# ISL6236A_DEMO.net
KiCad netlist of a schematic drawn in Altium Designer
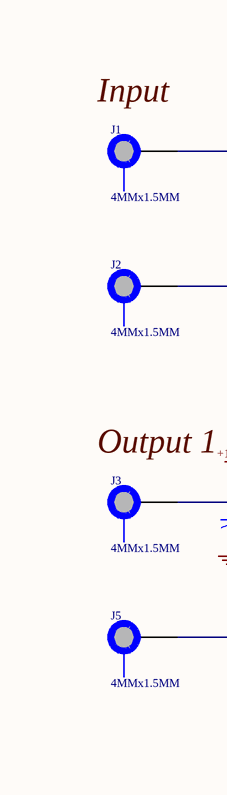
[diagram p0: ISL6236A_DEMO.SchDoc, left]
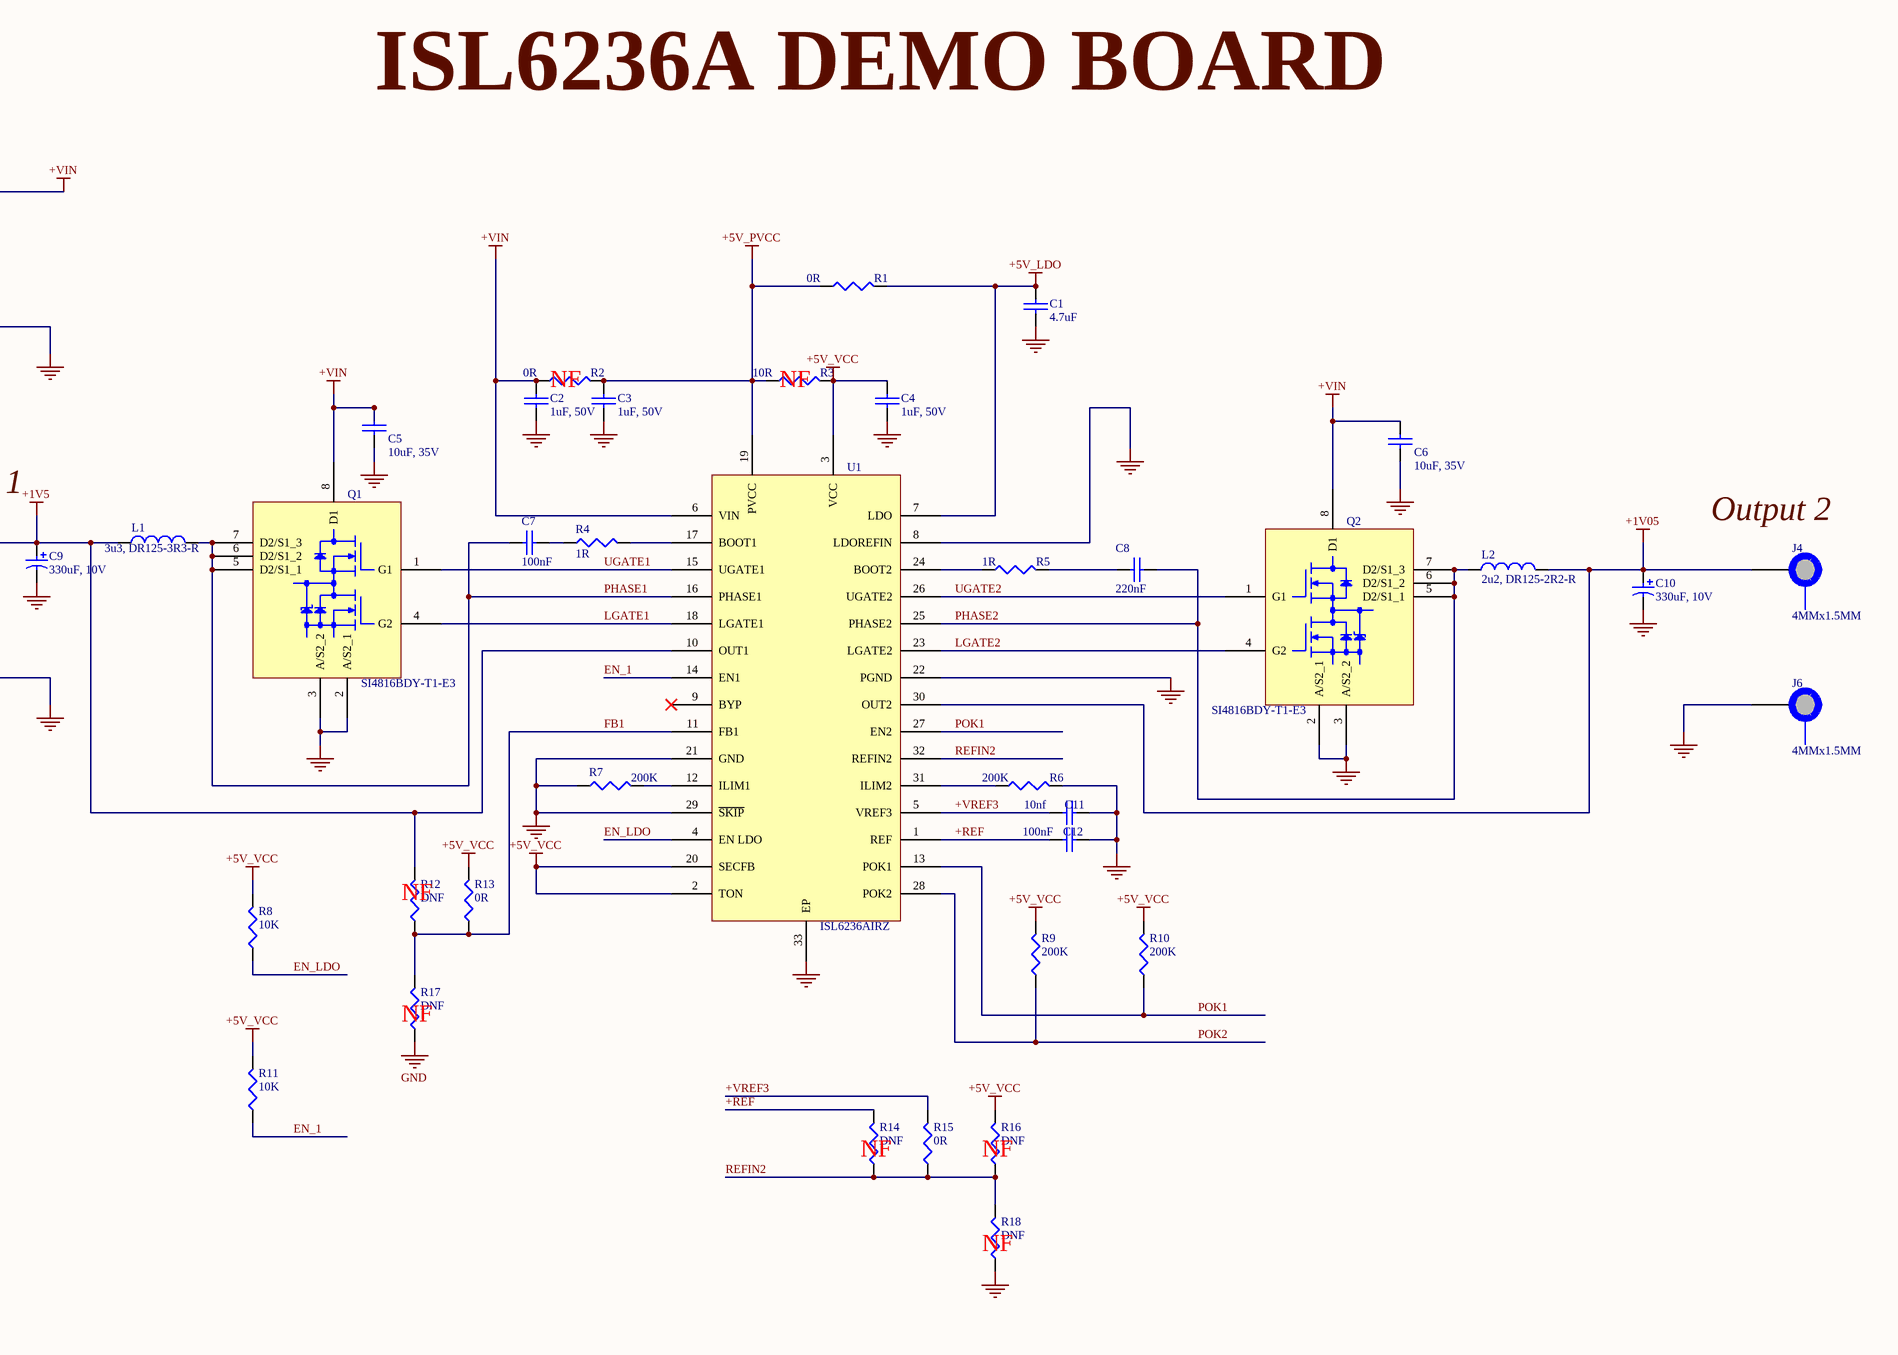
[diagram p1: ISL6236A_DEMO.SchDoc, right]

(export (version "E")
  (design (tool "Eeschema 10.0.6"))
  (components
    (comp (ref "C1")
      (value "4.7uF")
      (description "C Series 1206 4.7 uF 50 V ±10 % Tolerance X5R SMT Multilayer Ceramic Capacitor")
      (fields
        (field (name "MANUFACTURER") "TDK")
        (field (name "MANUFACTURER PART NUMBER") "C3216X5R1H475K160AB")
      )
      (libsource (lib "ISL6236A_DEMO") (part "C3216X5R1H475K160AB"))
    )
    (comp (ref "C2")
      (value "1uF, 50V")
      (description "C Series 0805 1 uF 50 V ±10% Tolerance X7R SMT Multilayer Ceramic Capacitor")
      (fields
        (field (name "MANUFACTURER") "TDK")
        (field (name "MANUFACTURER PART NUMBER") "C2012X7R1H105K125AB")
      )
      (libsource (lib "ISL6236A_DEMO") (part "C2012X7R1H105K125AB"))
    )
    (comp (ref "C3")
      (value "1uF, 50V")
      (description "C Series 0805 1 uF 50 V ±10% Tolerance X7R SMT Multilayer Ceramic Capacitor")
      (fields
        (field (name "MANUFACTURER") "TDK")
        (field (name "MANUFACTURER PART NUMBER") "C2012X7R1H105K125AB")
      )
      (libsource (lib "ISL6236A_DEMO") (part "C2012X7R1H105K125AB"))
    )
    (comp (ref "C4")
      (value "1uF, 50V")
      (description "C Series 0805 1 uF 50 V ±10% Tolerance X7R SMT Multilayer Ceramic Capacitor")
      (fields
        (field (name "MANUFACTURER") "TDK")
        (field (name "MANUFACTURER PART NUMBER") "C2012X7R1H105K125AB")
      )
      (libsource (lib "ISL6236A_DEMO") (part "C2012X7R1H105K125AB"))
    )
    (comp (ref "C5")
      (value "10uF, 35V")
      (fields
        (field (name "MANUFACTURER") "Yageo Group")
        (field (name "MANUFACTURER PART NUMBER") "C1210C106K6PAC7210")
        (field (name "TOLERANCE") "10%")
      )
      (libsource (lib "ISL6236A_DEMO") (part "C1210C106K6PAC7210"))
    )
    (comp (ref "C6")
      (value "10uF, 35V")
      (fields
        (field (name "MANUFACTURER") "Yageo Group")
        (field (name "MANUFACTURER PART NUMBER") "C1210C106K6PAC7210")
        (field (name "TOLERANCE") "10%")
      )
      (libsource (lib "ISL6236A_DEMO") (part "C1210C106K6PAC7210"))
    )
    (comp (ref "C7")
      (value "100nF")
      (description "Cap Ceramic 0.1uF 50V X7R 10% Pad SMD 0805 Flexible Termination 125C Automotive Medical T/R")
      (fields
        (field (name "MANUFACTURER") "Yageo Group")
        (field (name "MANUFACTURER PART NUMBER") "C0805X104K5RACTU")
      )
      (libsource (lib "ISL6236A_DEMO") (part "C0805X104K5RACTU"))
    )
    (comp (ref "C8")
      (value "220nF")
      (description "50V 220nF X7R ±10% 0805 Multilayer Ceramic Capacitors MLCC - SMD/SMT ROHS")
      (fields
        (field (name "MANUFACTURER") "Yageo Group")
        (field (name "MANUFACTURER PART NUMBER") "C0805C224K5RACTU")
      )
      (libsource (lib "ISL6236A_DEMO") (part "C0805C224K5RACTU"))
    )
    (comp (ref "C9")
      (value "330uF, 10V")
      (description "Cap Tant Solid 330uF 10V X CASE 20% (7.3 X 4.3 X 4mm) SMD 7343-43 T/R")
      (fields
        (field (name "MANUFACTURER") "Yageo Group")
        (field (name "MANUFACTURER PART NUMBER") "T530X337M010ATE004")
      )
      (libsource (lib "ISL6236A_DEMO") (part "T530X337M010ATE004"))
    )
    (comp (ref "C10")
      (value "330uF, 10V")
      (description "Cap Tant Solid 330uF 10V X CASE 20% (7.3 X 4.3 X 4mm) SMD 7343-43 T/R")
      (fields
        (field (name "MANUFACTURER") "Yageo Group")
        (field (name "MANUFACTURER PART NUMBER") "T530X337M010ATE004")
      )
      (libsource (lib "ISL6236A_DEMO") (part "T530X337M010ATE004"))
    )
    (comp (ref "C11")
      (value "10nf")
      (description "Multilayer Ceramic Capacitors Mlcc - Smd/Smt 50V 0.01Uf X7R 0805 10%")
      (fields
        (field (name "MANUFACTURER") "Yageo Group")
        (field (name "MANUFACTURER PART NUMBER") "C0805C103K5RACTU")
      )
      (libsource (lib "ISL6236A_DEMO") (part "C0805C103K5RACTU"))
    )
    (comp (ref "C12")
      (value "100nF")
      (description "Cap Ceramic 0.1uF 50V X7R 10% Pad SMD 0805 Flexible Termination 125C Automotive Medical T/R")
      (fields
        (field (name "MANUFACTURER") "Yageo Group")
        (field (name "MANUFACTURER PART NUMBER") "C0805X104K5RACTU")
      )
      (libsource (lib "ISL6236A_DEMO") (part "C0805X104K5RACTU"))
    )
    (comp (ref "J1")
      (value "4MMx1.5MM")
      (description "pad with a hole 4mm x 1.5mm")
      (libsource (lib "ISL6236A_DEMO") (part "PAD_WITH_HOLE_4MM_1MM5"))
    )
    (comp (ref "J2")
      (value "4MMx1.5MM")
      (description "pad with a hole 4mm x 1.5mm")
      (libsource (lib "ISL6236A_DEMO") (part "PAD_WITH_HOLE_4MM_1MM5"))
    )
    (comp (ref "J3")
      (value "4MMx1.5MM")
      (description "pad with a hole 4mm x 1.5mm")
      (libsource (lib "ISL6236A_DEMO") (part "PAD_WITH_HOLE_4MM_1MM5"))
    )
    (comp (ref "J4")
      (value "4MMx1.5MM")
      (description "pad with a hole 4mm x 1.5mm")
      (libsource (lib "ISL6236A_DEMO") (part "PAD_WITH_HOLE_4MM_1MM5"))
    )
    (comp (ref "J5")
      (value "4MMx1.5MM")
      (description "pad with a hole 4mm x 1.5mm")
      (libsource (lib "ISL6236A_DEMO") (part "PAD_WITH_HOLE_4MM_1MM5"))
    )
    (comp (ref "J6")
      (value "4MMx1.5MM")
      (description "pad with a hole 4mm x 1.5mm")
      (libsource (lib "ISL6236A_DEMO") (part "PAD_WITH_HOLE_4MM_1MM5"))
    )
    (comp (ref "L1")
      (value "3u3, DR125-3R3-R")
      (description "Inductor Power Shielded Drum Core 3.3uH 20% 100KHz Ferrite 9.26A 6.3mOhm DCR T/R")
      (fields (field (name "MANUFACTURER") "Eaton") (field (name "MANUFACTURER PART NUMBER") "DR125-3R3-R"))
      (libsource (lib "ISL6236A_DEMO") (part "DR125-3R3-R"))
    )
    (comp (ref "L2")
      (value "2u2, DR125-2R2-R")
      (description "Inductor Power Shielded Drum Core 2.2uH 20% 100KHz Ferrite 10.9A 4.5mOhm DCR T/R")
      (fields (field (name "MANUFACTURER") "Eaton") (field (name "MANUFACTURER PART NUMBER") "DR125-2R2-R"))
      (libsource (lib "ISL6236A_DEMO") (part "DR125-2R2-R"))
    )
    (comp (ref "Q1")
      (value "SI4816BDY-T1-E3")
      (description "Transistor MOSFET Array Dual N-CH 30V 5.8A/8.2A 8-Pin SOIC T/R")
      (fields (field (name "MANUFACTURER") "Vishay"))
      (libsource (lib "ISL6236A_DEMO") (part "SI4816BDY-T1-E3"))
    )
    (comp (ref "Q2")
      (value "SI4816BDY-T1-E3")
      (description "Transistor MOSFET Array Dual N-CH 30V 5.8A/8.2A 8-Pin SOIC T/R")
      (fields (field (name "MANUFACTURER") "Vishay"))
      (libsource (lib "") (part "SI4816BDY-T1-E3_1"))
    )
    (comp (ref "R1")
      (value "0R")
      (description "Zero Ohm Resistor, Jumper, 0805 [2012 Metric], Thick Film, 125 mW, 2 A, Surface Mount Device")
      (fields
        (field (name "MANUFACTURER") "Yageo Group")
        (field (name "MANUFACTURER PART NUMBER") "AC0805JR-070RL")
      )
      (libsource (lib "ISL6236A_DEMO") (part "AC0805JR-070RL"))
    )
    (comp (ref "R2")
      (value "0R")
      (description "Zero Ohm Resistor, Jumper, 0805 [2012 Metric], Thick Film, 125 mW, 2 A, Surface Mount Device")
      (fields
        (field (name "MANUFACTURER") "Yageo Group")
        (field (name "MANUFACTURER PART NUMBER") "AC0805JR-070RL")
      )
      (libsource (lib "ISL6236A_DEMO") (part "AC0805JR-070RL"))
    )
    (comp (ref "R3")
      (value "10R")
      (description "Res Thick Film 0805 10 Ohm 1% 0.125W(1/8W) ±100ppm/C Pad SMD T/R Automotive AEC-Q200")
      (fields
        (field (name "MANUFACTURER") "Yageo Group")
        (field (name "MANUFACTURER PART NUMBER") "AC0805FR-1310RL")
      )
      (libsource (lib "ISL6236A_DEMO") (part "AC0805FR-1310RL"))
    )
    (comp (ref "R4")
      (value "1R")
      (description "Res Thick Film 0805 1 Ohm 1% 0.125W(1/8W) ±200ppm/C Pad SMD T/R Automotive AEC-Q200")
      (fields
        (field (name "MANUFACTURER") "Yageo Group")
        (field (name "MANUFACTURER PART NUMBER") "AC0805FR-071RL")
      )
      (libsource (lib "ISL6236A_DEMO") (part "AC0805FR-071RL"))
    )
    (comp (ref "R5")
      (value "1R")
      (description "Res Thick Film 0805 1 Ohm 1% 0.125W(1/8W) ±200ppm/C Pad SMD T/R Automotive AEC-Q200")
      (fields
        (field (name "MANUFACTURER") "Yageo Group")
        (field (name "MANUFACTURER PART NUMBER") "AC0805FR-071RL")
      )
      (libsource (lib "ISL6236A_DEMO") (part "AC0805FR-071RL"))
    )
    (comp (ref "R6")
      (value "200K")
      (description "Res Thick Film 0805 200K Ohm 1% 0.125W(1/8W) ±100ppm/C Pad SMD T/R Automotive AEC-Q200")
      (fields
        (field (name "MANUFACTURER") "Yageo Group")
        (field (name "MANUFACTURER PART NUMBER") "AC0805FR-07200KL")
      )
      (libsource (lib "ISL6236A_DEMO") (part "AC0805FR-07200KL"))
    )
    (comp (ref "R7")
      (value "200K")
      (description "Res Thick Film 0805 200K Ohm 1% 0.125W(1/8W) ±100ppm/C Pad SMD T/R Automotive AEC-Q200")
      (fields
        (field (name "MANUFACTURER") "Yageo Group")
        (field (name "MANUFACTURER PART NUMBER") "AC0805FR-07200KL")
      )
      (libsource (lib "ISL6236A_DEMO") (part "AC0805FR-07200KL"))
    )
    (comp (ref "R8")
      (value "10K")
      (description "Res Thick Film 0805 10K Ohm 1% 0.125W(1/8W) ±100ppm/C Pad SMD Automotive T/R")
      (fields
        (field (name "MANUFACTURER") "Yageo Group")
        (field (name "MANUFACTURER PART NUMBER") "AC0805FR-0710KL")
      )
      (libsource (lib "ISL6236A_DEMO") (part "AC0805FR-0710KL"))
    )
    (comp (ref "R9")
      (value "200K")
      (description "Res Thick Film 0805 200K Ohm 1% 0.125W(1/8W) ±100ppm/C Pad SMD T/R Automotive AEC-Q200")
      (fields
        (field (name "MANUFACTURER") "Yageo Group")
        (field (name "MANUFACTURER PART NUMBER") "AC0805FR-07200KL")
      )
      (libsource (lib "ISL6236A_DEMO") (part "AC0805FR-07200KL"))
    )
    (comp (ref "R10")
      (value "200K")
      (description "Res Thick Film 0805 200K Ohm 1% 0.125W(1/8W) ±100ppm/C Pad SMD T/R Automotive AEC-Q200")
      (fields
        (field (name "MANUFACTURER") "Yageo Group")
        (field (name "MANUFACTURER PART NUMBER") "AC0805FR-07200KL")
      )
      (libsource (lib "ISL6236A_DEMO") (part "AC0805FR-07200KL"))
    )
    (comp (ref "R11")
      (value "10K")
      (description "Res Thick Film 0805 10K Ohm 1% 0.125W(1/8W) ±100ppm/C Pad SMD Automotive T/R")
      (fields
        (field (name "MANUFACTURER") "Yageo Group")
        (field (name "MANUFACTURER PART NUMBER") "AC0805FR-0710KL")
      )
      (libsource (lib "ISL6236A_DEMO") (part "AC0805FR-0710KL"))
    )
    (comp (ref "R12") (value "DNF") (libsource (lib "ISL6236A_DEMO") (part "RES")))
    (comp (ref "R13")
      (value "0R")
      (description "Zero Ohm Resistor, Jumper, 0805 [2012 Metric], Thick Film, 125 mW, 2 A, Surface Mount Device")
      (fields
        (field (name "MANUFACTURER") "Yageo Group")
        (field (name "MANUFACTURER PART NUMBER") "AC0805JR-070RL")
      )
      (libsource (lib "ISL6236A_DEMO") (part "AC0805JR-070RL"))
    )
    (comp (ref "R14") (value "DNF") (libsource (lib "ISL6236A_DEMO") (part "RES")))
    (comp (ref "R15")
      (value "0R")
      (description "Zero Ohm Resistor, Jumper, 0805 [2012 Metric], Thick Film, 125 mW, 2 A, Surface Mount Device")
      (fields
        (field (name "MANUFACTURER") "Yageo Group")
        (field (name "MANUFACTURER PART NUMBER") "AC0805JR-070RL")
      )
      (libsource (lib "ISL6236A_DEMO") (part "AC0805JR-070RL"))
    )
    (comp (ref "R16") (value "DNF") (libsource (lib "ISL6236A_DEMO") (part "RES")))
    (comp (ref "R17") (value "DNF") (libsource (lib "ISL6236A_DEMO") (part "RES")))
    (comp (ref "R18") (value "DNF") (libsource (lib "ISL6236A_DEMO") (part "RES")))
    (comp (ref "U1")
      (value "ISL6236AIRZ")
      (description "Soft Sw PWM Cntrlr 2-OUT Power Supply Controller 200KHz/300KHz/400KHz/500KHz 32-Pin QFN EP")
      (fields (field (name "MANUFACTURER") "Renesas"))
      (libsource (lib "ISL6236A_DEMO") (part "ISL6236AIRZ"))
    )
  )
  (nets
    (net (code "1") (name "+1V05") (class "Default")
      (node (ref "C10") (pin "1") (pinfunction "1_1") (pintype "passive"))
      (node (ref "J4") (pin "1") (pinfunction "1_1") (pintype "passive"))
      (node (ref "L2") (pin "2") (pinfunction "2_2") (pintype "passive"))
      (node (ref "U1") (pin "30") (pinfunction "OUT2_30") (pintype "passive"))
    )
    (net (code "2") (name "+1V5") (class "Default")
      (node (ref "C9") (pin "1") (pinfunction "1_1") (pintype "passive"))
      (node (ref "J3") (pin "1") (pinfunction "1_1") (pintype "passive"))
      (node (ref "L1") (pin "1") (pinfunction "1_1") (pintype "passive"))
      (node (ref "R12") (pin "2") (pinfunction "2_2") (pintype "passive"))
      (node (ref "U1") (pin "10") (pinfunction "OUT1_10") (pintype "passive"))
    )
    (net (code "3") (name "+5V_LDO") (class "Default")
      (node (ref "C1") (pin "2") (pinfunction "2_2") (pintype "passive"))
      (node (ref "R1") (pin "2") (pinfunction "2_2") (pintype "passive"))
      (node (ref "U1") (pin "7") (pinfunction "LDO_7") (pintype "passive"))
    )
    (net (code "4") (name "+5V_PVCC") (class "Default")
      (node (ref "C3") (pin "1") (pinfunction "1_1") (pintype "passive"))
      (node (ref "R1") (pin "1") (pinfunction "1_1") (pintype "passive"))
      (node (ref "R2") (pin "2") (pinfunction "2_2") (pintype "passive"))
      (node (ref "R3") (pin "1") (pinfunction "1_1") (pintype "passive"))
      (node (ref "U1") (pin "19") (pinfunction "PVCC_19") (pintype "passive"))
    )
    (net (code "5") (name "+5V_VCC") (class "Default")
      (node (ref "C4") (pin "1") (pinfunction "1_1") (pintype "passive"))
      (node (ref "R10") (pin "2") (pinfunction "2_2") (pintype "passive"))
      (node (ref "R11") (pin "2") (pinfunction "2_2") (pintype "passive"))
      (node (ref "R13") (pin "2") (pinfunction "2_2") (pintype "passive"))
      (node (ref "R16") (pin "2") (pinfunction "2_2") (pintype "passive"))
      (node (ref "R3") (pin "2") (pinfunction "2_2") (pintype "passive"))
      (node (ref "R8") (pin "2") (pinfunction "2_2") (pintype "passive"))
      (node (ref "R9") (pin "2") (pinfunction "2_2") (pintype "passive"))
      (node (ref "U1") (pin "2") (pinfunction "TON_2") (pintype "passive"))
      (node (ref "U1") (pin "20") (pinfunction "SECFB_20") (pintype "passive"))
      (node (ref "U1") (pin "3") (pinfunction "VCC_3") (pintype "passive"))
    )
    (net (code "6") (name "+VIN") (class "Default")
      (node (ref "C2") (pin "1") (pinfunction "1_1") (pintype "passive"))
      (node (ref "C5") (pin "2") (pinfunction "2_2") (pintype "passive"))
      (node (ref "C6") (pin "2") (pinfunction "2_2") (pintype "passive"))
      (node (ref "J1") (pin "1") (pinfunction "1_1") (pintype "passive"))
      (node (ref "Q1") (pin "8") (pinfunction "D1_8") (pintype "passive"))
      (node (ref "Q2") (pin "8") (pinfunction "D1_8") (pintype "passive"))
      (node (ref "R2") (pin "1") (pinfunction "1_1") (pintype "passive"))
      (node (ref "U1") (pin "6") (pinfunction "VIN_6") (pintype "passive"))
    )
    (net (code "7") (name "/+REF") (class "Default")
      (node (ref "C12") (pin "1") (pinfunction "1_1") (pintype "passive"))
      (node (ref "R14") (pin "2") (pinfunction "2_2") (pintype "passive"))
      (node (ref "U1") (pin "1") (pinfunction "REF_1") (pintype "passive"))
    )
    (net (code "8") (name "/+VREF3") (class "Default")
      (node (ref "C11") (pin "1") (pinfunction "1_1") (pintype "passive"))
      (node (ref "R15") (pin "2") (pinfunction "2_2") (pintype "passive"))
      (node (ref "U1") (pin "5") (pinfunction "VREF3_5") (pintype "passive"))
    )
    (net (code "9") (name "/EN_1") (class "Default")
      (node (ref "R11") (pin "1") (pinfunction "1_1") (pintype "passive"))
      (node (ref "U1") (pin "14") (pinfunction "EN1_14") (pintype "passive"))
    )
    (net (code "10") (name "/EN_LDO") (class "Default")
      (node (ref "R8") (pin "1") (pinfunction "1_1") (pintype "passive"))
      (node (ref "U1") (pin "4") (pinfunction "EN_LDO_4") (pintype "passive"))
    )
    (net (code "11") (name "/FB1") (class "Default")
      (node (ref "R12") (pin "1") (pinfunction "1_1") (pintype "passive"))
      (node (ref "R13") (pin "1") (pinfunction "1_1") (pintype "passive"))
      (node (ref "R17") (pin "2") (pinfunction "2_2") (pintype "passive"))
      (node (ref "U1") (pin "11") (pinfunction "FB1_11") (pintype "passive"))
    )
    (net (code "12") (name "/LGATE1") (class "Default")
      (node (ref "Q1") (pin "4") (pinfunction "G2_4") (pintype "passive"))
      (node (ref "U1") (pin "18") (pinfunction "LGATE1_18") (pintype "passive"))
    )
    (net (code "13") (name "/LGATE2") (class "Default")
      (node (ref "Q2") (pin "4") (pinfunction "G2_4") (pintype "passive"))
      (node (ref "U1") (pin "23") (pinfunction "LGATE2_23") (pintype "passive"))
    )
    (net (code "14") (name "/PHASE1") (class "Default")
      (node (ref "C7") (pin "1") (pinfunction "1_1") (pintype "passive"))
      (node (ref "L1") (pin "2") (pinfunction "2_2") (pintype "passive"))
      (node (ref "Q1") (pin "5") (pinfunction "D2/S1_1_5") (pintype "passive"))
      (node (ref "Q1") (pin "6") (pinfunction "D2/S1_2_6") (pintype "passive"))
      (node (ref "Q1") (pin "7") (pinfunction "D2/S1_3_7") (pintype "passive"))
      (node (ref "U1") (pin "16") (pinfunction "PHASE1_16") (pintype "passive"))
    )
    (net (code "15") (name "/PHASE2") (class "Default")
      (node (ref "C8") (pin "2") (pinfunction "2_2") (pintype "passive"))
      (node (ref "L2") (pin "1") (pinfunction "1_1") (pintype "passive"))
      (node (ref "Q2") (pin "5") (pinfunction "D2/S1_1_5") (pintype "passive"))
      (node (ref "Q2") (pin "6") (pinfunction "D2/S1_2_6") (pintype "passive"))
      (node (ref "Q2") (pin "7") (pinfunction "D2/S1_3_7") (pintype "passive"))
      (node (ref "U1") (pin "25") (pinfunction "PHASE2_25") (pintype "passive"))
    )
    (net (code "16") (name "/POK1") (class "Default")
      (node (ref "R10") (pin "1") (pinfunction "1_1") (pintype "passive"))
      (node (ref "U1") (pin "13") (pinfunction "POK1_13") (pintype "passive"))
      (node (ref "U1") (pin "27") (pinfunction "EN2_27") (pintype "passive"))
    )
    (net (code "17") (name "/POK2") (class "Default")
      (node (ref "R9") (pin "1") (pinfunction "1_1") (pintype "passive"))
      (node (ref "U1") (pin "28") (pinfunction "POK2_28") (pintype "passive"))
    )
    (net (code "18") (name "/REFIN2") (class "Default")
      (node (ref "R14") (pin "1") (pinfunction "1_1") (pintype "passive"))
      (node (ref "R15") (pin "1") (pinfunction "1_1") (pintype "passive"))
      (node (ref "R16") (pin "1") (pinfunction "1_1") (pintype "passive"))
      (node (ref "R18") (pin "2") (pinfunction "2_2") (pintype "passive"))
      (node (ref "U1") (pin "32") (pinfunction "REFIN2_32") (pintype "passive"))
    )
    (net (code "19") (name "/UGATE1") (class "Default")
      (node (ref "Q1") (pin "1") (pinfunction "G1_1") (pintype "passive"))
      (node (ref "U1") (pin "15") (pinfunction "UGATE1_15") (pintype "passive"))
    )
    (net (code "20") (name "/UGATE2") (class "Default")
      (node (ref "Q2") (pin "1") (pinfunction "G1_1") (pintype "passive"))
      (node (ref "U1") (pin "26") (pinfunction "UGATE2_26") (pintype "passive"))
    )
    (net (code "21") (name "GND") (class "Default")
      (node (ref "C1") (pin "1") (pinfunction "1_1") (pintype "passive"))
      (node (ref "C10") (pin "2") (pinfunction "2_2") (pintype "passive"))
      (node (ref "C11") (pin "2") (pinfunction "2_2") (pintype "passive"))
      (node (ref "C12") (pin "2") (pinfunction "2_2") (pintype "passive"))
      (node (ref "C2") (pin "2") (pinfunction "2_2") (pintype "passive"))
      (node (ref "C3") (pin "2") (pinfunction "2_2") (pintype "passive"))
      (node (ref "C4") (pin "2") (pinfunction "2_2") (pintype "passive"))
      (node (ref "C5") (pin "1") (pinfunction "1_1") (pintype "passive"))
      (node (ref "C6") (pin "1") (pinfunction "1_1") (pintype "passive"))
      (node (ref "C9") (pin "2") (pinfunction "2_2") (pintype "passive"))
      (node (ref "J2") (pin "1") (pinfunction "1_1") (pintype "passive"))
      (node (ref "J5") (pin "1") (pinfunction "1_1") (pintype "passive"))
      (node (ref "J6") (pin "1") (pinfunction "1_1") (pintype "passive"))
      (node (ref "Q1") (pin "2") (pinfunction "A/S2_1_2") (pintype "passive"))
      (node (ref "Q1") (pin "3") (pinfunction "A/S2_2_3") (pintype "passive"))
      (node (ref "Q2") (pin "2") (pinfunction "A/S2_1_2") (pintype "passive"))
      (node (ref "Q2") (pin "3") (pinfunction "A/S2_2_3") (pintype "passive"))
      (node (ref "R17") (pin "1") (pinfunction "1_1") (pintype "passive"))
      (node (ref "R18") (pin "1") (pinfunction "1_1") (pintype "passive"))
      (node (ref "R6") (pin "2") (pinfunction "2_2") (pintype "passive"))
      (node (ref "R7") (pin "1") (pinfunction "1_1") (pintype "passive"))
      (node (ref "U1") (pin "21") (pinfunction "GND_21") (pintype "passive"))
      (node (ref "U1") (pin "22") (pinfunction "PGND_22") (pintype "passive"))
      (node (ref "U1") (pin "29") (pinfunction "~{SKIP}_29") (pintype "passive"))
      (node (ref "U1") (pin "33") (pinfunction "EP_33") (pintype "passive"))
      (node (ref "U1") (pin "8") (pinfunction "LDOREFIN_8") (pintype "passive"))
    )
    (net (code "22") (name "Net-(C7-Pad2)") (class "Default")
      (node (ref "C7") (pin "2") (pinfunction "2_2") (pintype "passive"))
      (node (ref "R4") (pin "1") (pinfunction "1_1") (pintype "passive"))
    )
    (net (code "23") (name "Net-(C8-Pad1)") (class "Default")
      (node (ref "C8") (pin "1") (pinfunction "1_1") (pintype "passive"))
      (node (ref "R5") (pin "2") (pinfunction "2_2") (pintype "passive"))
    )
    (net (code "24") (name "Net-(U1-BOOT1)") (class "Default")
      (node (ref "R4") (pin "2") (pinfunction "2_2") (pintype "passive"))
      (node (ref "U1") (pin "17") (pinfunction "BOOT1_17") (pintype "passive"))
    )
    (net (code "25") (name "Net-(U1-BOOT2)") (class "Default")
      (node (ref "R5") (pin "1") (pinfunction "1_1") (pintype "passive"))
      (node (ref "U1") (pin "24") (pinfunction "BOOT2_24") (pintype "passive"))
    )
    (net (code "26") (name "Net-(U1-ILIM1)") (class "Default")
      (node (ref "R7") (pin "2") (pinfunction "2_2") (pintype "passive"))
      (node (ref "U1") (pin "12") (pinfunction "ILIM1_12") (pintype "passive"))
    )
    (net (code "27") (name "Net-(U1-ILIM2)") (class "Default")
      (node (ref "R6") (pin "1") (pinfunction "1_1") (pintype "passive"))
      (node (ref "U1") (pin "31") (pinfunction "ILIM2_31") (pintype "passive"))
    )
    (net (code "28") (name "unconnected-(U1-BYP-Pad9)") (class "Default")
      (node (ref "U1") (pin "9") (pinfunction "BYP_9") (pintype "passive+no_connect"))
    )
  )
)
